# SCH_Naked_ATMega_2560_2021-08-20.net
KiCad netlist of a schematic drawn in EasyEDA
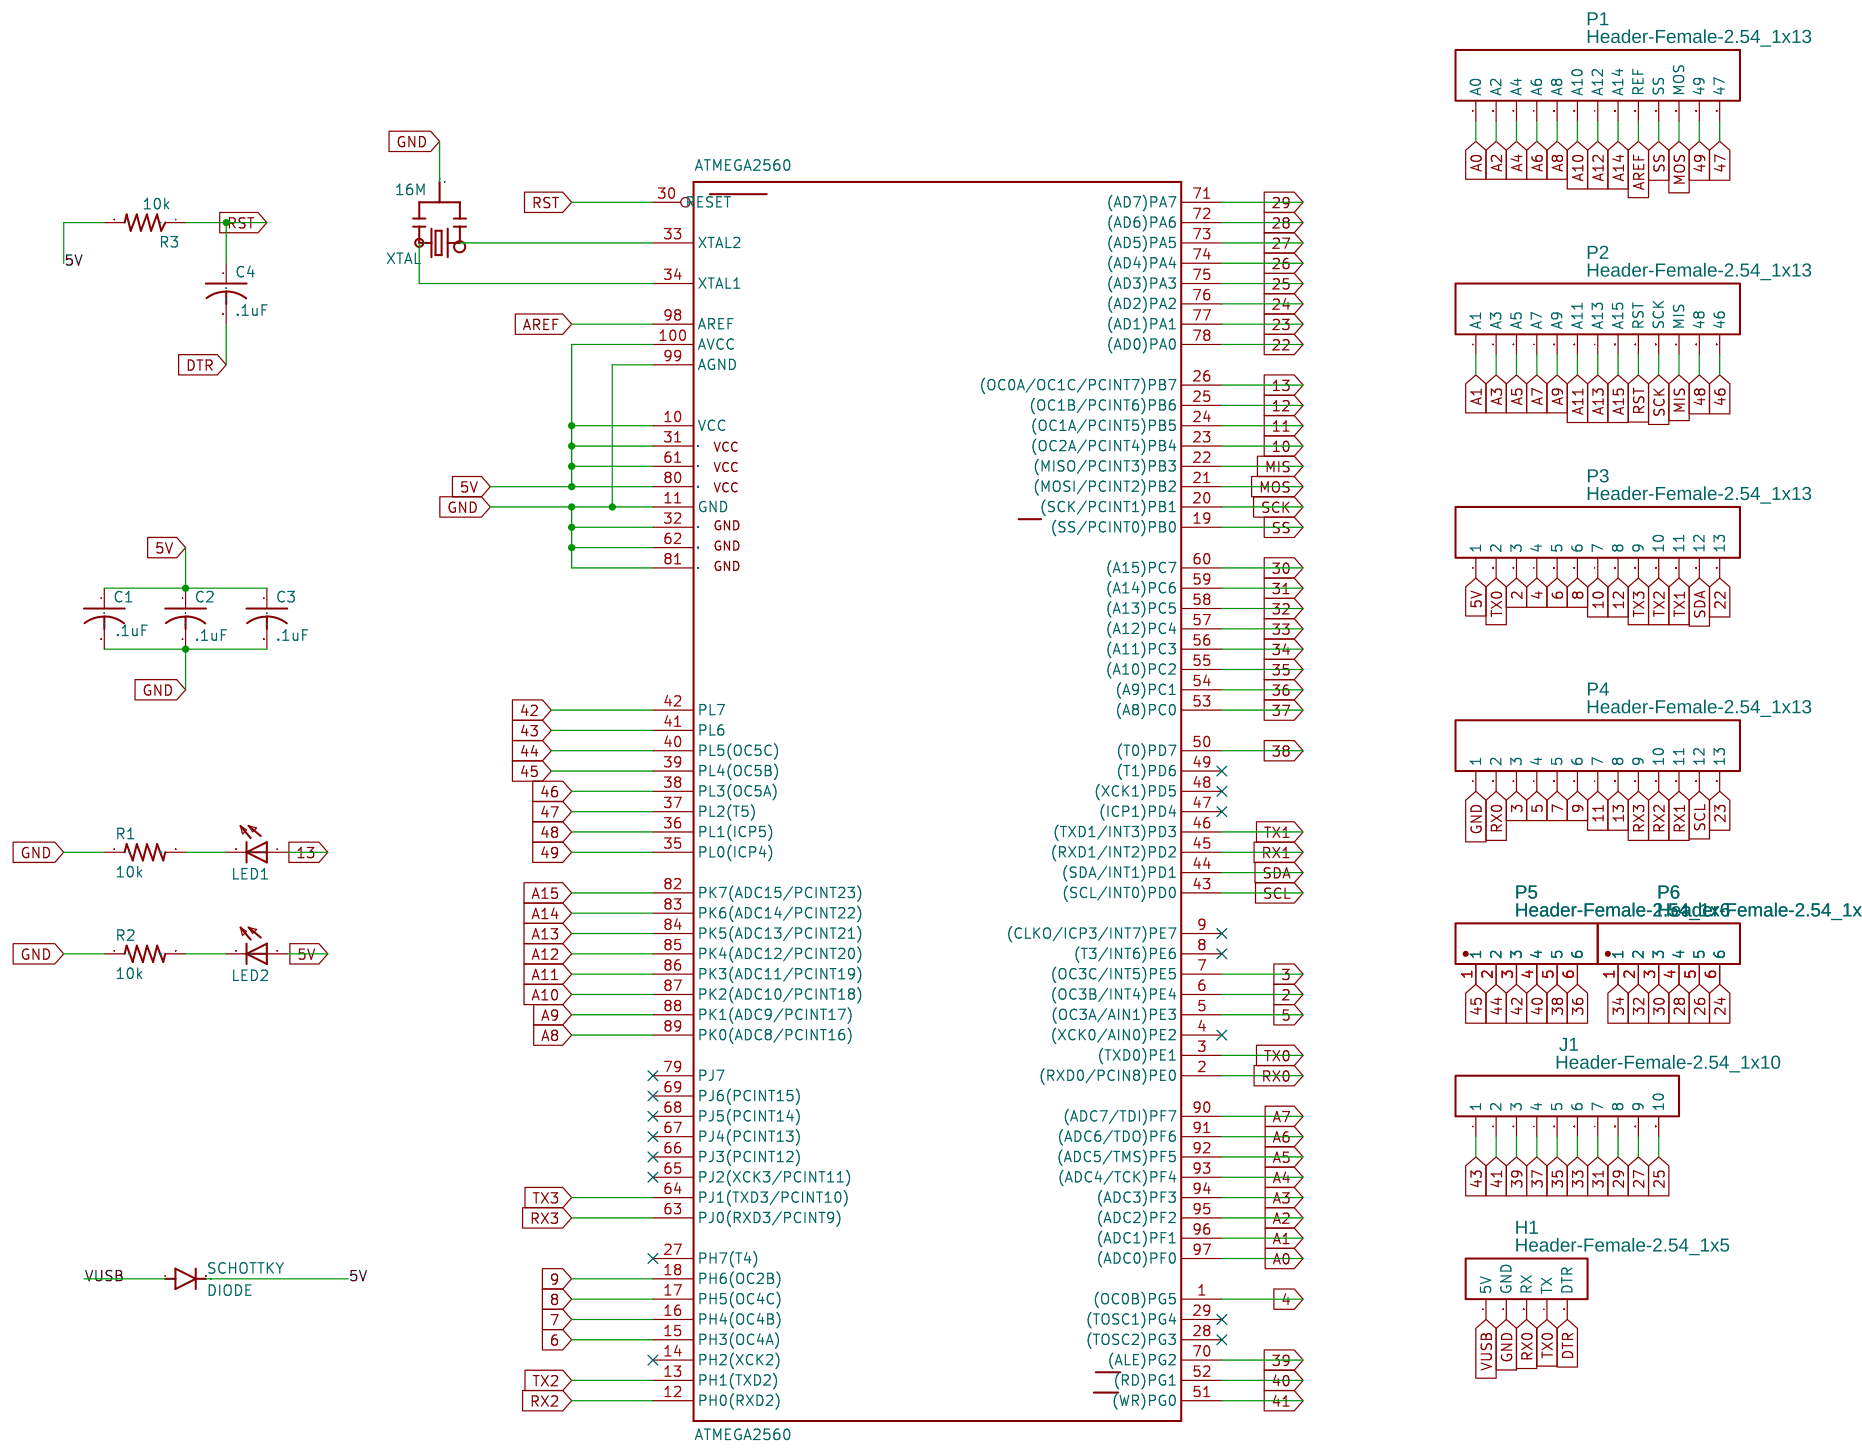
[diagram p0: schematic sheet]

(export (version "E")
  (design (tool "Eeschema 10.0.6"))
  (components
    (comp (ref "ATMEGA2560") (value "ATMEGA2560") (libsource (lib "") (part "Unknown_470_-340")))
    (comp (ref "C1") (value "CAPACITOR-SMD-0805") (libsource (lib "") (part "Unknown_60_-430")))
    (comp (ref "C2") (value ".1uF") (libsource (lib "") (part "Unknown_100_-430")))
    (comp (ref "C3") (value ".1uF") (libsource (lib "") (part "Unknown_140_-430")))
    (comp (ref "C4") (value ".1uF") (libsource (lib "") (part "Unknown_120_-590")))
    (comp (ref "H1")
      (value "Header-Female-2.54_1x5")
      (fields
        (field (name "BOM_Manufacturer Part") "2.54mm 1*5p Female header")
        (field (name "BOM_Supplier Part") "C50950")
      )
      (libsource (lib "") (part "Header-Female-2.54_1x5"))
    )
    (comp (ref "J1")
      (value "Header-Female-2.54_1x10")
      (fields
        (field (name "BOM_Manufacturer Part") "2.54mm 1*10P Straight Female header Gold-plated")
        (field (name "BOM_Supplier Part") "C35445")
      )
      (libsource (lib "") (part "Header-Female-2.54_1x10"))
    )
    (comp (ref "LED1") (value "L") (libsource (lib "") (part "Unknown_140_-310")))
    (comp (ref "LED2") (value "L") (libsource (lib "") (part "Unknown_140_-260")))
    (comp (ref "P1")
      (value "Header-Female-2.54_1x13")
      (fields
        (field (name "BOM_Manufacturer Part") "Female header 2.54-1*13P")
        (field (name "BOM_Supplier Part") "C52709")
      )
      (libsource (lib "") (part "Header-Female-2.54_1x13"))
    )
    (comp (ref "P2")
      (value "Header-Female-2.54_1x13")
      (fields
        (field (name "BOM_Manufacturer Part") "Female header 2.54-1*13P")
        (field (name "BOM_Supplier Part") "C52709")
      )
      (libsource (lib "") (part "Header-Female-2.54_1x13_1"))
    )
    (comp (ref "P3")
      (value "Header-Female-2.54_1x13")
      (fields
        (field (name "BOM_Manufacturer Part") "Female header 2.54-1*13P")
        (field (name "BOM_Supplier Part") "C52709")
      )
      (libsource (lib "") (part "Header-Female-2.54_1x13_2"))
    )
    (comp (ref "P4")
      (value "Header-Female-2.54_1x13")
      (fields
        (field (name "BOM_Manufacturer Part") "Female header 2.54-1*13P")
        (field (name "BOM_Supplier Part") "C52709")
      )
      (libsource (lib "") (part "Header-Female-2.54_1x13_2"))
    )
    (comp (ref "P5")
      (value "Header-Female-2.54_1x6")
      (fields
        (field (name "BOM_Manufacturer Part") "Female header 1*6p")
        (field (name "BOM_Supplier Part") "C40877")
      )
      (libsource (lib "") (part "Header-Female-2.54_1x6"))
    )
    (comp (ref "P6")
      (value "Header-Female-2.54_1x6")
      (fields
        (field (name "BOM_Manufacturer Part") "Female header 1*6p")
        (field (name "BOM_Supplier Part") "C40877")
      )
      (libsource (lib "") (part "Header-Female-2.54_1x6"))
    )
    (comp (ref "R1") (value "10k") (libsource (lib "") (part "Unknown_80_-310")))
    (comp (ref "R2") (value "10k") (libsource (lib "") (part "Unknown_80_-260")))
    (comp (ref "R3") (value "10k") (libsource (lib "") (part "Unknown_80_-620")))
    (comp (ref "SCHOTTKY") (value "DIODE") (libsource (lib "") (part "Unknown_100_-100")))
    (comp (ref "XTAL") (value "16M") (libsource (lib "") (part "Unknown_225_-620")))
  )
  (nets
    (net (code "1") (name "2") (class "Default")
      (node (ref "ATMEGA2560") (pin "6") (pinfunction "(OC3B/INT4)PE4_6") (pintype "bidirectional"))
      (node (ref "P3") (pin "3") (pinfunction "3_3") (pintype "input"))
    )
    (net (code "2") (name "3") (class "Default")
      (node (ref "ATMEGA2560") (pin "7") (pinfunction "(OC3C/INT5)PE5_7") (pintype "bidirectional"))
      (node (ref "P4") (pin "3") (pinfunction "3_3") (pintype "input"))
    )
    (net (code "3") (name "4") (class "Default")
      (node (ref "ATMEGA2560") (pin "1") (pinfunction "(OC0B)PG5_1") (pintype "bidirectional"))
      (node (ref "P3") (pin "4") (pinfunction "4_4") (pintype "input"))
    )
    (net (code "4") (name "5") (class "Default")
      (node (ref "ATMEGA2560") (pin "5") (pinfunction "(OC3A/AIN1)PE3_5") (pintype "bidirectional"))
      (node (ref "P4") (pin "4") (pinfunction "4_4") (pintype "input"))
    )
    (net (code "5") (name "5V") (class "Default")
      (node (ref "ATMEGA2560") (pin "10") (pinfunction "VCC_10") (pintype "bidirectional"))
      (node (ref "ATMEGA2560") (pin "100") (pinfunction "AVCC_100") (pintype "bidirectional"))
      (node (ref "ATMEGA2560") (pin "31") (pinfunction "VCC1_31") (pintype "bidirectional"))
      (node (ref "ATMEGA2560") (pin "61") (pinfunction "VCC2_61") (pintype "bidirectional"))
      (node (ref "ATMEGA2560") (pin "80") (pinfunction "VCC3_80") (pintype "bidirectional"))
      (node (ref "C1") (pin "1") (pinfunction "1_1") (pintype "bidirectional"))
      (node (ref "C2") (pin "1") (pinfunction "1_1") (pintype "bidirectional"))
      (node (ref "C3") (pin "1") (pinfunction "1_1") (pintype "bidirectional"))
      (node (ref "LED2") (pin "1") (pinfunction "A_1") (pintype "bidirectional"))
      (node (ref "P3") (pin "1") (pinfunction "1_1") (pintype "input"))
      (node (ref "R3") (pin "2") (pinfunction "2_2") (pintype "bidirectional"))
      (node (ref "SCHOTTKY") (pin "2") (pinfunction "C_2") (pintype "bidirectional"))
    )
    (net (code "6") (name "6") (class "Default")
      (node (ref "ATMEGA2560") (pin "15") (pinfunction "PH3(OC4A)_15") (pintype "bidirectional"))
      (node (ref "P3") (pin "5") (pinfunction "5_5") (pintype "input"))
    )
    (net (code "7") (name "7") (class "Default")
      (node (ref "ATMEGA2560") (pin "16") (pinfunction "PH4(OC4B)_16") (pintype "bidirectional"))
      (node (ref "P4") (pin "5") (pinfunction "5_5") (pintype "input"))
    )
    (net (code "8") (name "8") (class "Default")
      (node (ref "ATMEGA2560") (pin "17") (pinfunction "PH5(OC4C)_17") (pintype "bidirectional"))
      (node (ref "P3") (pin "6") (pinfunction "6_6") (pintype "input"))
    )
    (net (code "9") (name "9") (class "Default")
      (node (ref "ATMEGA2560") (pin "18") (pinfunction "PH6(OC2B)_18") (pintype "bidirectional"))
      (node (ref "P4") (pin "6") (pinfunction "6_6") (pintype "input"))
    )
    (net (code "10") (name "10") (class "Default")
      (node (ref "ATMEGA2560") (pin "23") (pinfunction "(OC2A/PCINT4)PB4_23") (pintype "bidirectional"))
      (node (ref "P3") (pin "7") (pinfunction "7_7") (pintype "input"))
    )
    (net (code "11") (name "11") (class "Default")
      (node (ref "ATMEGA2560") (pin "24") (pinfunction "(OC1A/PCINT5)PB5_24") (pintype "bidirectional"))
      (node (ref "P4") (pin "7") (pinfunction "7_7") (pintype "input"))
    )
    (net (code "12") (name "12") (class "Default")
      (node (ref "ATMEGA2560") (pin "25") (pinfunction "(OC1B/PCINT6)PB6_25") (pintype "bidirectional"))
      (node (ref "P3") (pin "8") (pinfunction "8_8") (pintype "input"))
    )
    (net (code "13") (name "13") (class "Default")
      (node (ref "ATMEGA2560") (pin "26") (pinfunction "(OC0A/OC1C/PCINT7)PB7_26") (pintype "bidirectional"))
      (node (ref "LED1") (pin "1") (pinfunction "A_1") (pintype "bidirectional"))
      (node (ref "P4") (pin "8") (pinfunction "8_8") (pintype "input"))
    )
    (net (code "14") (name "22") (class "Default")
      (node (ref "ATMEGA2560") (pin "78") (pinfunction "(AD0)PA0_78") (pintype "bidirectional"))
      (node (ref "P3") (pin "13") (pinfunction "13_13") (pintype "input"))
    )
    (net (code "15") (name "23") (class "Default")
      (node (ref "ATMEGA2560") (pin "77") (pinfunction "(AD1)PA1_77") (pintype "bidirectional"))
      (node (ref "P4") (pin "13") (pinfunction "13_13") (pintype "input"))
    )
    (net (code "16") (name "24") (class "Default")
      (node (ref "ATMEGA2560") (pin "76") (pinfunction "(AD2)PA2_76") (pintype "bidirectional"))
      (node (ref "P6") (pin "6") (pinfunction "6_6") (pintype "unspecified"))
    )
    (net (code "17") (name "25") (class "Default")
      (node (ref "ATMEGA2560") (pin "75") (pinfunction "(AD3)PA3_75") (pintype "bidirectional"))
      (node (ref "J1") (pin "10") (pinfunction "10_10") (pintype "input"))
    )
    (net (code "18") (name "26") (class "Default")
      (node (ref "ATMEGA2560") (pin "74") (pinfunction "(AD4)PA4_74") (pintype "bidirectional"))
      (node (ref "P6") (pin "5") (pinfunction "5_5") (pintype "unspecified"))
    )
    (net (code "19") (name "27") (class "Default")
      (node (ref "ATMEGA2560") (pin "73") (pinfunction "(AD5)PA5_73") (pintype "bidirectional"))
      (node (ref "J1") (pin "9") (pinfunction "9_9") (pintype "input"))
    )
    (net (code "20") (name "28") (class "Default")
      (node (ref "ATMEGA2560") (pin "72") (pinfunction "(AD6)PA6_72") (pintype "bidirectional"))
      (node (ref "P6") (pin "4") (pinfunction "4_4") (pintype "unspecified"))
    )
    (net (code "21") (name "29") (class "Default")
      (node (ref "ATMEGA2560") (pin "71") (pinfunction "(AD7)PA7_71") (pintype "bidirectional"))
      (node (ref "J1") (pin "8") (pinfunction "8_8") (pintype "input"))
    )
    (net (code "22") (name "30") (class "Default")
      (node (ref "ATMEGA2560") (pin "60") (pinfunction "(A15)PC7_60") (pintype "bidirectional"))
      (node (ref "P6") (pin "3") (pinfunction "3_3") (pintype "unspecified"))
    )
    (net (code "23") (name "31") (class "Default")
      (node (ref "ATMEGA2560") (pin "59") (pinfunction "(A14)PC6_59") (pintype "bidirectional"))
      (node (ref "J1") (pin "7") (pinfunction "7_7") (pintype "input"))
    )
    (net (code "24") (name "32") (class "Default")
      (node (ref "ATMEGA2560") (pin "58") (pinfunction "(A13)PC5_58") (pintype "bidirectional"))
      (node (ref "P6") (pin "2") (pinfunction "2_2") (pintype "unspecified"))
    )
    (net (code "25") (name "33") (class "Default")
      (node (ref "ATMEGA2560") (pin "57") (pinfunction "(A12)PC4_57") (pintype "bidirectional"))
      (node (ref "J1") (pin "6") (pinfunction "6_6") (pintype "input"))
    )
    (net (code "26") (name "34") (class "Default")
      (node (ref "ATMEGA2560") (pin "56") (pinfunction "(A11)PC3_56") (pintype "bidirectional"))
      (node (ref "P6") (pin "1") (pinfunction "1_1") (pintype "unspecified"))
    )
    (net (code "27") (name "35") (class "Default")
      (node (ref "ATMEGA2560") (pin "55") (pinfunction "(A10)PC2_55") (pintype "bidirectional"))
      (node (ref "J1") (pin "5") (pinfunction "5_5") (pintype "input"))
    )
    (net (code "28") (name "36") (class "Default")
      (node (ref "ATMEGA2560") (pin "54") (pinfunction "(A9)PC1_54") (pintype "bidirectional"))
      (node (ref "P5") (pin "6") (pinfunction "6_6") (pintype "unspecified"))
    )
    (net (code "29") (name "37") (class "Default")
      (node (ref "ATMEGA2560") (pin "53") (pinfunction "(A8)PC0_53") (pintype "bidirectional"))
      (node (ref "J1") (pin "4") (pinfunction "4_4") (pintype "input"))
    )
    (net (code "30") (name "38") (class "Default")
      (node (ref "ATMEGA2560") (pin "50") (pinfunction "(T0)PD7_50") (pintype "bidirectional"))
      (node (ref "P5") (pin "5") (pinfunction "5_5") (pintype "unspecified"))
    )
    (net (code "31") (name "39") (class "Default")
      (node (ref "ATMEGA2560") (pin "70") (pinfunction "(ALE)PG2_70") (pintype "bidirectional"))
      (node (ref "J1") (pin "3") (pinfunction "3_3") (pintype "input"))
    )
    (net (code "32") (name "40") (class "Default")
      (node (ref "ATMEGA2560") (pin "52") (pinfunction "(RD)PG1_52") (pintype "bidirectional"))
      (node (ref "P5") (pin "4") (pinfunction "4_4") (pintype "unspecified"))
    )
    (net (code "33") (name "41") (class "Default")
      (node (ref "ATMEGA2560") (pin "51") (pinfunction "(WR)PG0_51") (pintype "bidirectional"))
      (node (ref "J1") (pin "2") (pinfunction "2_2") (pintype "input"))
    )
    (net (code "34") (name "42") (class "Default")
      (node (ref "ATMEGA2560") (pin "42") (pinfunction "PL7_42") (pintype "bidirectional"))
      (node (ref "P5") (pin "3") (pinfunction "3_3") (pintype "unspecified"))
    )
    (net (code "35") (name "43") (class "Default")
      (node (ref "ATMEGA2560") (pin "41") (pinfunction "PL6_41") (pintype "bidirectional"))
      (node (ref "J1") (pin "1") (pinfunction "1_1") (pintype "input"))
    )
    (net (code "36") (name "44") (class "Default")
      (node (ref "ATMEGA2560") (pin "40") (pinfunction "PL5(OC5C)_40") (pintype "bidirectional"))
      (node (ref "P5") (pin "2") (pinfunction "2_2") (pintype "unspecified"))
    )
    (net (code "37") (name "45") (class "Default")
      (node (ref "ATMEGA2560") (pin "39") (pinfunction "PL4(OC5B)_39") (pintype "bidirectional"))
      (node (ref "P5") (pin "1") (pinfunction "1_1") (pintype "unspecified"))
    )
    (net (code "38") (name "46") (class "Default")
      (node (ref "ATMEGA2560") (pin "38") (pinfunction "PL3(OC5A)_38") (pintype "bidirectional"))
      (node (ref "P2") (pin "13") (pinfunction "46_13") (pintype "input"))
    )
    (net (code "39") (name "47") (class "Default")
      (node (ref "ATMEGA2560") (pin "37") (pinfunction "PL2(T5)_37") (pintype "bidirectional"))
      (node (ref "P1") (pin "13") (pinfunction "47_13") (pintype "input"))
    )
    (net (code "40") (name "48") (class "Default")
      (node (ref "ATMEGA2560") (pin "36") (pinfunction "PL1(ICP5)_36") (pintype "bidirectional"))
      (node (ref "P2") (pin "12") (pinfunction "48_12") (pintype "input"))
    )
    (net (code "41") (name "49") (class "Default")
      (node (ref "ATMEGA2560") (pin "35") (pinfunction "PL0(ICP4)_35") (pintype "bidirectional"))
      (node (ref "P1") (pin "12") (pinfunction "49_12") (pintype "input"))
    )
    (net (code "42") (name "A0") (class "Default")
      (node (ref "ATMEGA2560") (pin "97") (pinfunction "(ADC0)PF0_97") (pintype "bidirectional"))
      (node (ref "P1") (pin "1") (pinfunction "A0_1") (pintype "input"))
    )
    (net (code "43") (name "A1") (class "Default")
      (node (ref "ATMEGA2560") (pin "96") (pinfunction "(ADC1)PF1_96") (pintype "bidirectional"))
      (node (ref "P2") (pin "1") (pinfunction "A1_1") (pintype "input"))
    )
    (net (code "44") (name "A2") (class "Default")
      (node (ref "ATMEGA2560") (pin "95") (pinfunction "(ADC2)PF2_95") (pintype "bidirectional"))
      (node (ref "P1") (pin "2") (pinfunction "A2_2") (pintype "input"))
    )
    (net (code "45") (name "A3") (class "Default")
      (node (ref "ATMEGA2560") (pin "94") (pinfunction "(ADC3)PF3_94") (pintype "bidirectional"))
      (node (ref "P2") (pin "2") (pinfunction "A3_2") (pintype "input"))
    )
    (net (code "46") (name "A4") (class "Default")
      (node (ref "ATMEGA2560") (pin "93") (pinfunction "(ADC4/TCK)PF4_93") (pintype "bidirectional"))
      (node (ref "P1") (pin "3") (pinfunction "A4_3") (pintype "input"))
    )
    (net (code "47") (name "A5") (class "Default")
      (node (ref "ATMEGA2560") (pin "92") (pinfunction "(ADC5/TMS)PF5_92") (pintype "bidirectional"))
      (node (ref "P2") (pin "3") (pinfunction "A5_3") (pintype "input"))
    )
    (net (code "48") (name "A6") (class "Default")
      (node (ref "ATMEGA2560") (pin "91") (pinfunction "(ADC6/TDO)PF6_91") (pintype "bidirectional"))
      (node (ref "P1") (pin "4") (pinfunction "A6_4") (pintype "input"))
    )
    (net (code "49") (name "A7") (class "Default")
      (node (ref "ATMEGA2560") (pin "90") (pinfunction "(ADC7/TDI)PF7_90") (pintype "bidirectional"))
      (node (ref "P2") (pin "4") (pinfunction "A7_4") (pintype "input"))
    )
    (net (code "50") (name "A8") (class "Default")
      (node (ref "ATMEGA2560") (pin "89") (pinfunction "PK0(ADC8/PCINT16)_89") (pintype "bidirectional"))
      (node (ref "P1") (pin "5") (pinfunction "A8_5") (pintype "input"))
    )
    (net (code "51") (name "A9") (class "Default")
      (node (ref "ATMEGA2560") (pin "88") (pinfunction "PK1(ADC9/PCINT17)_88") (pintype "bidirectional"))
      (node (ref "P2") (pin "5") (pinfunction "A9_5") (pintype "input"))
    )
    (net (code "52") (name "A10") (class "Default")
      (node (ref "ATMEGA2560") (pin "87") (pinfunction "PK2(ADC10/PCINT18)_87") (pintype "bidirectional"))
      (node (ref "P1") (pin "6") (pinfunction "A10_6") (pintype "input"))
    )
    (net (code "53") (name "A11") (class "Default")
      (node (ref "ATMEGA2560") (pin "86") (pinfunction "PK3(ADC11/PCINT19)_86") (pintype "bidirectional"))
      (node (ref "P2") (pin "6") (pinfunction "A11_6") (pintype "input"))
    )
    (net (code "54") (name "A12") (class "Default")
      (node (ref "ATMEGA2560") (pin "85") (pinfunction "PK4(ADC12/PCINT20)_85") (pintype "bidirectional"))
      (node (ref "P1") (pin "7") (pinfunction "A12_7") (pintype "input"))
    )
    (net (code "55") (name "A13") (class "Default")
      (node (ref "ATMEGA2560") (pin "84") (pinfunction "PK5(ADC13/PCINT21)_84") (pintype "bidirectional"))
      (node (ref "P2") (pin "7") (pinfunction "A13_7") (pintype "input"))
    )
    (net (code "56") (name "A14") (class "Default")
      (node (ref "ATMEGA2560") (pin "83") (pinfunction "PK6(ADC14/PCINT22)_83") (pintype "bidirectional"))
      (node (ref "P1") (pin "8") (pinfunction "A14_8") (pintype "input"))
    )
    (net (code "57") (name "A15") (class "Default")
      (node (ref "ATMEGA2560") (pin "82") (pinfunction "PK7(ADC15/PCINT23)_82") (pintype "bidirectional"))
      (node (ref "P2") (pin "8") (pinfunction "A15_8") (pintype "input"))
    )
    (net (code "58") (name "AREF") (class "Default")
      (node (ref "ATMEGA2560") (pin "98") (pinfunction "AREF_98") (pintype "bidirectional"))
      (node (ref "P1") (pin "9") (pinfunction "REF_9") (pintype "input"))
    )
    (net (code "59") (name "DTR") (class "Default")
      (node (ref "C4") (pin "2") (pinfunction "2_2") (pintype "bidirectional"))
      (node (ref "H1") (pin "5") (pinfunction "DTR_5") (pintype "input"))
    )
    (net (code "60") (name "GND") (class "Default")
      (node (ref "ATMEGA2560") (pin "11") (pinfunction "GND_11") (pintype "bidirectional"))
      (node (ref "ATMEGA2560") (pin "32") (pinfunction "GND1_32") (pintype "bidirectional"))
      (node (ref "ATMEGA2560") (pin "62") (pinfunction "GND2_62") (pintype "bidirectional"))
      (node (ref "ATMEGA2560") (pin "81") (pinfunction "GND3_81") (pintype "bidirectional"))
      (node (ref "ATMEGA2560") (pin "99") (pinfunction "AGND_99") (pintype "bidirectional"))
      (node (ref "C1") (pin "2") (pinfunction "2_2") (pintype "bidirectional"))
      (node (ref "C2") (pin "2") (pinfunction "2_2") (pintype "bidirectional"))
      (node (ref "C3") (pin "2") (pinfunction "2_2") (pintype "bidirectional"))
      (node (ref "H1") (pin "2") (pinfunction "GND_2") (pintype "input"))
      (node (ref "P4") (pin "1") (pinfunction "1_1") (pintype "input"))
      (node (ref "R1") (pin "1") (pinfunction "1_1") (pintype "bidirectional"))
      (node (ref "R2") (pin "1") (pinfunction "1_1") (pintype "bidirectional"))
      (node (ref "XTAL") (pin "2") (pinfunction "2_2") (pintype "bidirectional"))
    )
    (net (code "61") (name "MIS") (class "Default")
      (node (ref "ATMEGA2560") (pin "22") (pinfunction "(MISO/PCINT3)PB3_22") (pintype "bidirectional"))
      (node (ref "P2") (pin "11") (pinfunction "MIS_11") (pintype "input"))
    )
    (net (code "62") (name "MOS") (class "Default")
      (node (ref "ATMEGA2560") (pin "21") (pinfunction "(MOSI/PCINT2)PB2_21") (pintype "bidirectional"))
      (node (ref "P1") (pin "11") (pinfunction "MOS_11") (pintype "input"))
    )
    (net (code "63") (name "Net-(ATMEGA2560-XTAL1)") (class "Default")
      (node (ref "ATMEGA2560") (pin "34") (pinfunction "XTAL1_34") (pintype "bidirectional"))
      (node (ref "XTAL") (pin "3") (pinfunction "3_3") (pintype "bidirectional"))
    )
    (net (code "64") (name "Net-(ATMEGA2560-XTAL2)") (class "Default")
      (node (ref "ATMEGA2560") (pin "33") (pinfunction "XTAL2_33") (pintype "bidirectional"))
      (node (ref "XTAL") (pin "1") (pinfunction "1_1") (pintype "bidirectional"))
    )
    (net (code "65") (name "Net-(LED1-C)") (class "Default")
      (node (ref "LED1") (pin "2") (pinfunction "C_2") (pintype "bidirectional"))
      (node (ref "R1") (pin "2") (pinfunction "2_2") (pintype "bidirectional"))
    )
    (net (code "66") (name "Net-(LED2-C)") (class "Default")
      (node (ref "LED2") (pin "2") (pinfunction "C_2") (pintype "bidirectional"))
      (node (ref "R2") (pin "2") (pinfunction "2_2") (pintype "bidirectional"))
    )
    (net (code "67") (name "RST") (class "Default")
      (node (ref "ATMEGA2560") (pin "30") (pinfunction "RESET_30") (pintype "bidirectional"))
      (node (ref "C4") (pin "1") (pinfunction "1_1") (pintype "bidirectional"))
      (node (ref "P2") (pin "9") (pinfunction "RST_9") (pintype "input"))
      (node (ref "R3") (pin "1") (pinfunction "1_1") (pintype "bidirectional"))
    )
    (net (code "68") (name "RX0") (class "Default")
      (node (ref "ATMEGA2560") (pin "2") (pinfunction "(RXD0/PCIN8)PE0_2") (pintype "bidirectional"))
      (node (ref "H1") (pin "3") (pinfunction "RX_3") (pintype "input"))
      (node (ref "P4") (pin "2") (pinfunction "2_2") (pintype "input"))
    )
    (net (code "69") (name "RX1") (class "Default")
      (node (ref "ATMEGA2560") (pin "45") (pinfunction "(RXD1/INT2)PD2_45") (pintype "bidirectional"))
      (node (ref "P4") (pin "11") (pinfunction "11_11") (pintype "input"))
    )
    (net (code "70") (name "RX2") (class "Default")
      (node (ref "ATMEGA2560") (pin "12") (pinfunction "PH0(RXD2)_12") (pintype "bidirectional"))
      (node (ref "P4") (pin "10") (pinfunction "10_10") (pintype "input"))
    )
    (net (code "71") (name "RX3") (class "Default")
      (node (ref "ATMEGA2560") (pin "63") (pinfunction "PJ0(RXD3/PCINT9)_63") (pintype "bidirectional"))
      (node (ref "P4") (pin "9") (pinfunction "9_9") (pintype "input"))
    )
    (net (code "72") (name "SCK") (class "Default")
      (node (ref "ATMEGA2560") (pin "20") (pinfunction "(SCK/PCINT1)PB1_20") (pintype "bidirectional"))
      (node (ref "P2") (pin "10") (pinfunction "SCK_10") (pintype "input"))
    )
    (net (code "73") (name "SCL") (class "Default")
      (node (ref "ATMEGA2560") (pin "43") (pinfunction "(SCL/INT0)PD0_43") (pintype "bidirectional"))
      (node (ref "P4") (pin "12") (pinfunction "12_12") (pintype "input"))
    )
    (net (code "74") (name "SDA") (class "Default")
      (node (ref "ATMEGA2560") (pin "44") (pinfunction "(SDA/INT1)PD1_44") (pintype "bidirectional"))
      (node (ref "P3") (pin "12") (pinfunction "12_12") (pintype "input"))
    )
    (net (code "75") (name "SS") (class "Default")
      (node (ref "ATMEGA2560") (pin "19") (pinfunction "(SS/PCINT0)PB0_19") (pintype "bidirectional"))
      (node (ref "P1") (pin "10") (pinfunction "SS_10") (pintype "input"))
    )
    (net (code "76") (name "TX0") (class "Default")
      (node (ref "ATMEGA2560") (pin "3") (pinfunction "(TXD0)PE1_3") (pintype "bidirectional"))
      (node (ref "H1") (pin "4") (pinfunction "TX_4") (pintype "input"))
      (node (ref "P3") (pin "2") (pinfunction "2_2") (pintype "input"))
    )
    (net (code "77") (name "TX1") (class "Default")
      (node (ref "ATMEGA2560") (pin "46") (pinfunction "(TXD1/INT3)PD3_46") (pintype "bidirectional"))
      (node (ref "P3") (pin "11") (pinfunction "11_11") (pintype "input"))
    )
    (net (code "78") (name "TX2") (class "Default")
      (node (ref "ATMEGA2560") (pin "13") (pinfunction "PH1(TXD2)_13") (pintype "bidirectional"))
      (node (ref "P3") (pin "10") (pinfunction "10_10") (pintype "input"))
    )
    (net (code "79") (name "TX3") (class "Default")
      (node (ref "ATMEGA2560") (pin "64") (pinfunction "PJ1(TXD3/PCINT10)_64") (pintype "bidirectional"))
      (node (ref "P3") (pin "9") (pinfunction "9_9") (pintype "input"))
    )
    (net (code "80") (name "VUSB") (class "Default")
      (node (ref "H1") (pin "1") (pinfunction "5V_1") (pintype "input"))
      (node (ref "SCHOTTKY") (pin "1") (pinfunction "A_1") (pintype "bidirectional"))
    )
    (net (code "81") (name "unconnected-(ATMEGA2560-(CLKO{slash}ICP3{slash}INT7)PE7-Pad9)") (class "Default")
      (node (ref "ATMEGA2560") (pin "9") (pinfunction "(CLKO/ICP3/INT7)PE7_9") (pintype "bidirectional+no_connect"))
    )
    (net (code "82") (name "unconnected-(ATMEGA2560-(ICP1)PD4-Pad47)") (class "Default")
      (node (ref "ATMEGA2560") (pin "47") (pinfunction "(ICP1)PD4_47") (pintype "bidirectional+no_connect"))
    )
    (net (code "83") (name "unconnected-(ATMEGA2560-(T1)PD6-Pad49)") (class "Default")
      (node (ref "ATMEGA2560") (pin "49") (pinfunction "(T1)PD6_49") (pintype "bidirectional+no_connect"))
    )
    (net (code "84") (name "unconnected-(ATMEGA2560-(T3{slash}INT6)PE6-Pad8)") (class "Default")
      (node (ref "ATMEGA2560") (pin "8") (pinfunction "(T3/INT6)PE6_8") (pintype "bidirectional+no_connect"))
    )
    (net (code "85") (name "unconnected-(ATMEGA2560-(TOSC1)PG4-Pad29)") (class "Default")
      (node (ref "ATMEGA2560") (pin "29") (pinfunction "(TOSC1)PG4_29") (pintype "bidirectional+no_connect"))
    )
    (net (code "86") (name "unconnected-(ATMEGA2560-(TOSC2)PG3-Pad28)") (class "Default")
      (node (ref "ATMEGA2560") (pin "28") (pinfunction "(TOSC2)PG3_28") (pintype "bidirectional+no_connect"))
    )
    (net (code "87") (name "unconnected-(ATMEGA2560-(XCK0{slash}AIN0)PE2-Pad4)") (class "Default")
      (node (ref "ATMEGA2560") (pin "4") (pinfunction "(XCK0/AIN0)PE2_4") (pintype "bidirectional+no_connect"))
    )
    (net (code "88") (name "unconnected-(ATMEGA2560-(XCK1)PD5-Pad48)") (class "Default")
      (node (ref "ATMEGA2560") (pin "48") (pinfunction "(XCK1)PD5_48") (pintype "bidirectional+no_connect"))
    )
    (net (code "89") (name "unconnected-(ATMEGA2560-PH2(XCK2)-Pad14)") (class "Default")
      (node (ref "ATMEGA2560") (pin "14") (pinfunction "PH2(XCK2)_14") (pintype "bidirectional+no_connect"))
    )
    (net (code "90") (name "unconnected-(ATMEGA2560-PH7(T4)-Pad27)") (class "Default")
      (node (ref "ATMEGA2560") (pin "27") (pinfunction "PH7(T4)_27") (pintype "bidirectional+no_connect"))
    )
    (net (code "91") (name "unconnected-(ATMEGA2560-PJ2(XCK3{slash}PCINT11)-Pad65)") (class "Default")
      (node (ref "ATMEGA2560") (pin "65") (pinfunction "PJ2(XCK3/PCINT11)_65") (pintype "bidirectional+no_connect"))
    )
    (net (code "92") (name "unconnected-(ATMEGA2560-PJ3(PCINT12)-Pad66)") (class "Default")
      (node (ref "ATMEGA2560") (pin "66") (pinfunction "PJ3(PCINT12)_66") (pintype "bidirectional+no_connect"))
    )
    (net (code "93") (name "unconnected-(ATMEGA2560-PJ4(PCINT13)-Pad67)") (class "Default")
      (node (ref "ATMEGA2560") (pin "67") (pinfunction "PJ4(PCINT13)_67") (pintype "bidirectional+no_connect"))
    )
    (net (code "94") (name "unconnected-(ATMEGA2560-PJ5(PCINT14)-Pad68)") (class "Default")
      (node (ref "ATMEGA2560") (pin "68") (pinfunction "PJ5(PCINT14)_68") (pintype "bidirectional+no_connect"))
    )
    (net (code "95") (name "unconnected-(ATMEGA2560-PJ6(PCINT15)-Pad69)") (class "Default")
      (node (ref "ATMEGA2560") (pin "69") (pinfunction "PJ6(PCINT15)_69") (pintype "bidirectional+no_connect"))
    )
    (net (code "96") (name "unconnected-(ATMEGA2560-PJ7-Pad79)") (class "Default")
      (node (ref "ATMEGA2560") (pin "79") (pinfunction "PJ7_79") (pintype "bidirectional+no_connect"))
    )
  )
)
